# ULN2003_Motor_Driver_2021-05-13.net
KiCad netlist of a schematic drawn in EasyEDA
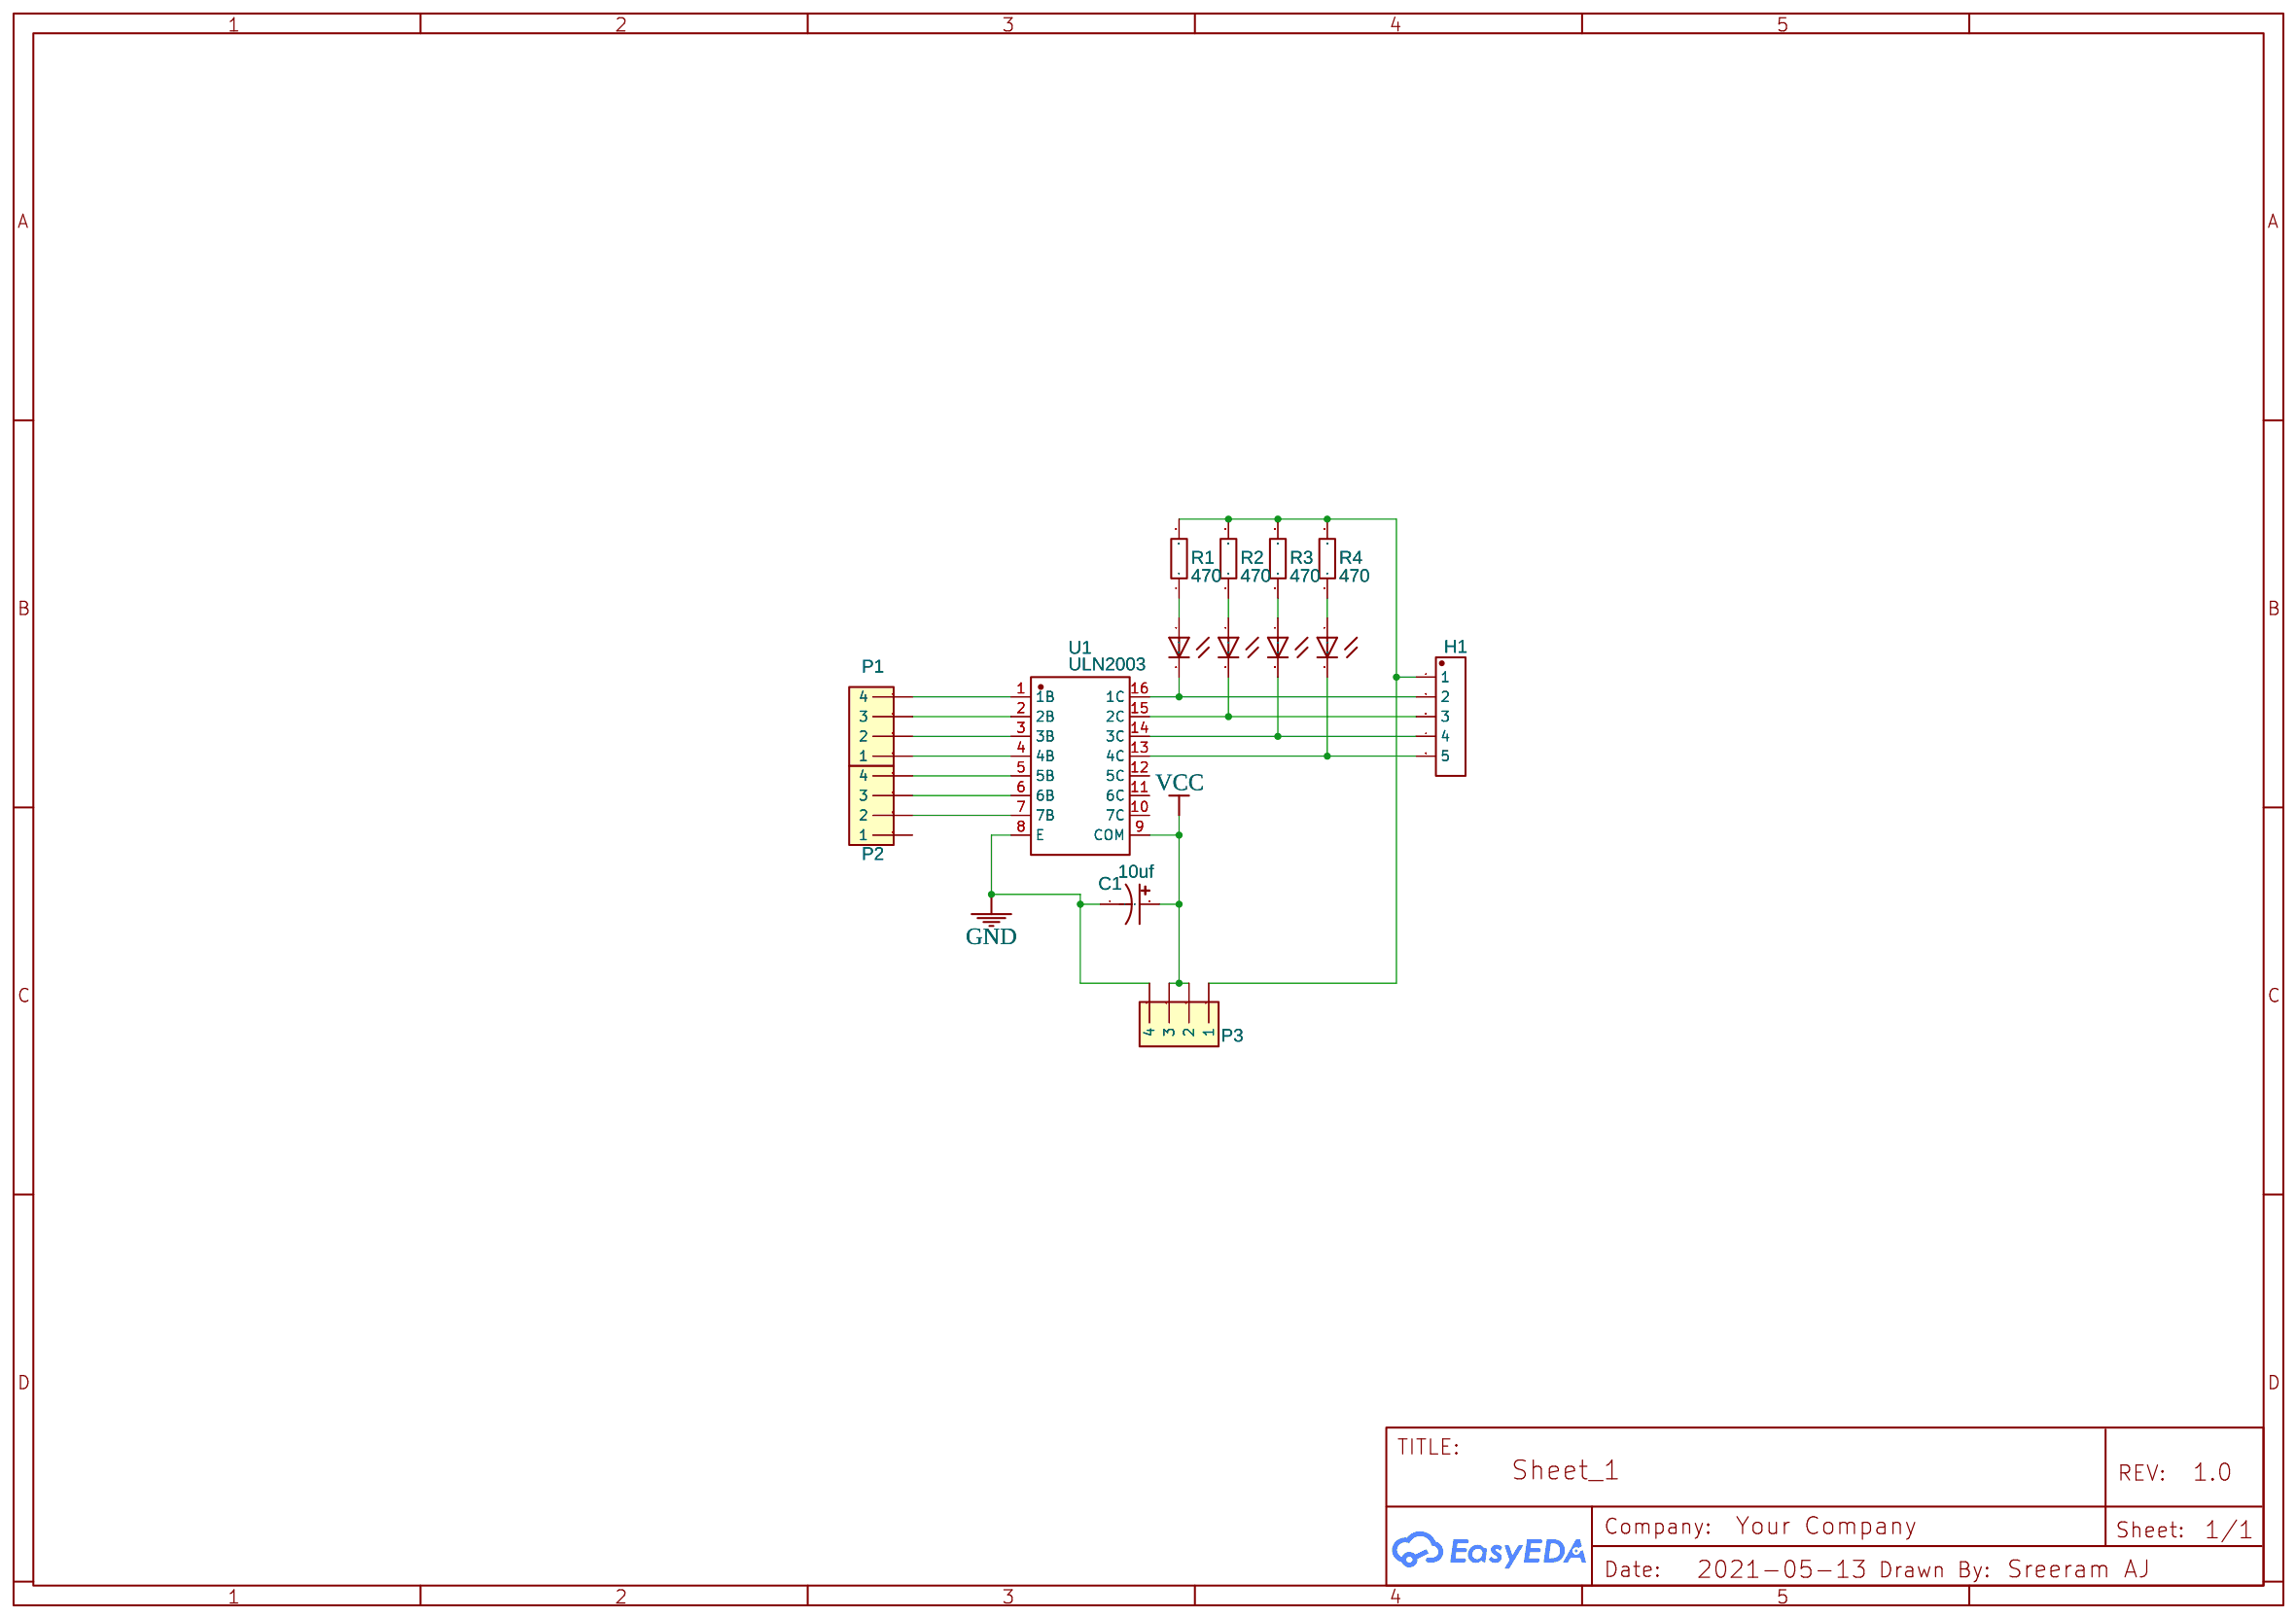
[diagram p0: schematic sheet]

(export (version "E")
  (design (tool "Eeschema 10.0.6"))
  (components
    (comp (ref "C1") (value "10uf") (libsource (lib "") (part "10UF-6.3V-20%(0603)(TANT)")))
    (comp (ref "H1")
      (value "Male Header 1*5P")
      (fields (field (name "BOM_Manufacturer Part") "210S-1*5P L=11.6MMGold-plated black"))
      (libsource (lib "") (part "Male Header 1*5P"))
    )
    (comp (ref "LED1") (value "LED - SMD - 0603") (libsource (lib "") (part "LED - SMD - 0603")))
    (comp (ref "LED2") (value "LED - SMD - 0603") (libsource (lib "") (part "LED - SMD - 0603")))
    (comp (ref "LED3") (value "LED - SMD - 0603") (libsource (lib "") (part "LED - SMD - 0603")))
    (comp (ref "LED4") (value "LED - SMD - 0603") (libsource (lib "") (part "LED - SMD - 0603")))
    (comp (ref "P1")
      (value "Male_header_bend_2.54mm_1*4P_copy")
      (fields (field (name "BOM_Supplier Part") "C35167"))
      (libsource (lib "") (part "Male_header_bend_2.54mm_1*4P_copy"))
    )
    (comp (ref "P2")
      (value "Male_header_bend_2.54mm_1*4P_copy")
      (fields (field (name "BOM_Supplier Part") "C35167"))
      (libsource (lib "") (part "Male_header_bend_2.54mm_1*4P_copy"))
    )
    (comp (ref "P3")
      (value "Male_header_bend_2.54mm_1*4P_copy")
      (fields (field (name "BOM_Supplier Part") "C35167"))
      (libsource (lib "") (part "Male_header_bend_2.54mm_1*4P_copy_1"))
    )
    (comp (ref "R1")
      (value "470")
      (fields
        (field (name "BOM_Manufacturer Part") "RS-03K102JT")
        (field (name "BOM_Supplier Part") "C73797")
      )
      (libsource (lib "") (part "1k Resistor SMD 0603 (C73797)"))
    )
    (comp (ref "R2")
      (value "470")
      (fields
        (field (name "BOM_Manufacturer Part") "RS-03K102JT")
        (field (name "BOM_Supplier Part") "C73797")
      )
      (libsource (lib "") (part "1k Resistor SMD 0603 (C73797)"))
    )
    (comp (ref "R3")
      (value "470")
      (fields
        (field (name "BOM_Manufacturer Part") "RS-03K102JT")
        (field (name "BOM_Supplier Part") "C73797")
      )
      (libsource (lib "") (part "1k Resistor SMD 0603 (C73797)"))
    )
    (comp (ref "R4")
      (value "470")
      (fields
        (field (name "BOM_Manufacturer Part") "RS-03K102JT")
        (field (name "BOM_Supplier Part") "C73797")
      )
      (libsource (lib "") (part "1k Resistor SMD 0603 (C73797)"))
    )
    (comp (ref "U1")
      (value "ULN2003")
      (fields (field (name "BOM_Supplier Part") "C2690547"))
      (libsource (lib "") (part "ULN2003"))
    )
  )
  (nets
    (net (code "1") (name "GND") (class "Default")
      (node (ref "C1") (pin "K") (pinfunction "-_K") (pintype "unspecified"))
      (node (ref "P3") (pin "4") (pinfunction "4_4") (pintype "input"))
      (node (ref "U1") (pin "8") (pinfunction "E_8") (pintype "unspecified"))
    )
    (net (code "2") (name "Net-(H1-Pad1)") (class "Default")
      (node (ref "H1") (pin "1") (pinfunction "1_1") (pintype "unspecified"))
      (node (ref "P3") (pin "1") (pinfunction "1_1") (pintype "input"))
      (node (ref "R1") (pin "2") (pinfunction "2_2") (pintype "input"))
      (node (ref "R2") (pin "2") (pinfunction "2_2") (pintype "input"))
      (node (ref "R3") (pin "2") (pinfunction "2_2") (pintype "input"))
      (node (ref "R4") (pin "2") (pinfunction "2_2") (pintype "input"))
    )
    (net (code "3") (name "Net-(LED1-Pad1)") (class "Default")
      (node (ref "LED1") (pin "1") (pinfunction "1_1") (pintype "unspecified"))
      (node (ref "R1") (pin "1") (pinfunction "1_1") (pintype "input"))
    )
    (net (code "4") (name "Net-(LED2-Pad1)") (class "Default")
      (node (ref "LED2") (pin "1") (pinfunction "1_1") (pintype "unspecified"))
      (node (ref "R2") (pin "1") (pinfunction "1_1") (pintype "input"))
    )
    (net (code "5") (name "Net-(LED3-Pad1)") (class "Default")
      (node (ref "LED3") (pin "1") (pinfunction "1_1") (pintype "unspecified"))
      (node (ref "R3") (pin "1") (pinfunction "1_1") (pintype "input"))
    )
    (net (code "6") (name "Net-(LED4-Pad1)") (class "Default")
      (node (ref "LED4") (pin "1") (pinfunction "1_1") (pintype "unspecified"))
      (node (ref "R4") (pin "1") (pinfunction "1_1") (pintype "input"))
    )
    (net (code "7") (name "Net-(U1-1B)") (class "Default")
      (node (ref "P1") (pin "4") (pinfunction "4_4") (pintype "input"))
      (node (ref "U1") (pin "1") (pinfunction "1B_1") (pintype "unspecified"))
    )
    (net (code "8") (name "Net-(U1-1C)") (class "Default")
      (node (ref "H1") (pin "2") (pinfunction "2_2") (pintype "unspecified"))
      (node (ref "LED1") (pin "2") (pinfunction "2_2") (pintype "unspecified"))
      (node (ref "U1") (pin "16") (pinfunction "1C_16") (pintype "unspecified"))
    )
    (net (code "9") (name "Net-(U1-2B)") (class "Default")
      (node (ref "P1") (pin "3") (pinfunction "3_3") (pintype "input"))
      (node (ref "U1") (pin "2") (pinfunction "2B_2") (pintype "unspecified"))
    )
    (net (code "10") (name "Net-(U1-2C)") (class "Default")
      (node (ref "H1") (pin "3") (pinfunction "3_3") (pintype "unspecified"))
      (node (ref "LED2") (pin "2") (pinfunction "2_2") (pintype "unspecified"))
      (node (ref "U1") (pin "15") (pinfunction "2C_15") (pintype "unspecified"))
    )
    (net (code "11") (name "Net-(U1-3B)") (class "Default")
      (node (ref "P1") (pin "2") (pinfunction "2_2") (pintype "input"))
      (node (ref "U1") (pin "3") (pinfunction "3B_3") (pintype "unspecified"))
    )
    (net (code "12") (name "Net-(U1-3C)") (class "Default")
      (node (ref "H1") (pin "4") (pinfunction "4_4") (pintype "unspecified"))
      (node (ref "LED3") (pin "2") (pinfunction "2_2") (pintype "unspecified"))
      (node (ref "U1") (pin "14") (pinfunction "3C_14") (pintype "unspecified"))
    )
    (net (code "13") (name "Net-(U1-4B)") (class "Default")
      (node (ref "P1") (pin "1") (pinfunction "1_1") (pintype "input"))
      (node (ref "U1") (pin "4") (pinfunction "4B_4") (pintype "unspecified"))
    )
    (net (code "14") (name "Net-(U1-4C)") (class "Default")
      (node (ref "H1") (pin "5") (pinfunction "5_5") (pintype "unspecified"))
      (node (ref "LED4") (pin "2") (pinfunction "2_2") (pintype "unspecified"))
      (node (ref "U1") (pin "13") (pinfunction "4C_13") (pintype "unspecified"))
    )
    (net (code "15") (name "Net-(U1-5B)") (class "Default")
      (node (ref "P2") (pin "4") (pinfunction "4_4") (pintype "input"))
      (node (ref "U1") (pin "5") (pinfunction "5B_5") (pintype "unspecified"))
    )
    (net (code "16") (name "Net-(U1-6B)") (class "Default")
      (node (ref "P2") (pin "3") (pinfunction "3_3") (pintype "input"))
      (node (ref "U1") (pin "6") (pinfunction "6B_6") (pintype "unspecified"))
    )
    (net (code "17") (name "Net-(U1-7B)") (class "Default")
      (node (ref "P2") (pin "2") (pinfunction "2_2") (pintype "input"))
      (node (ref "U1") (pin "7") (pinfunction "7B_7") (pintype "unspecified"))
    )
    (net (code "18") (name "VCC") (class "Default")
      (node (ref "C1") (pin "A") (pinfunction "+_A") (pintype "unspecified"))
      (node (ref "P3") (pin "2") (pinfunction "2_2") (pintype "input"))
      (node (ref "P3") (pin "3") (pinfunction "3_3") (pintype "input"))
      (node (ref "U1") (pin "9") (pinfunction "COM_9") (pintype "unspecified"))
    )
    (net (code "19") (name "unconnected-(P2-Pad1)") (class "Default")
      (node (ref "P2") (pin "1") (pinfunction "1_1") (pintype "input"))
    )
    (net (code "20") (name "unconnected-(U1-5C-Pad12)") (class "Default")
      (node (ref "U1") (pin "12") (pinfunction "5C_12") (pintype "unspecified"))
    )
    (net (code "21") (name "unconnected-(U1-6C-Pad11)") (class "Default")
      (node (ref "U1") (pin "11") (pinfunction "6C_11") (pintype "unspecified"))
    )
    (net (code "22") (name "unconnected-(U1-7C-Pad10)") (class "Default")
      (node (ref "U1") (pin "10") (pinfunction "7C_10") (pintype "unspecified"))
    )
  )
)
